# POWER.net
KiCad netlist of a schematic drawn in Altium Designer
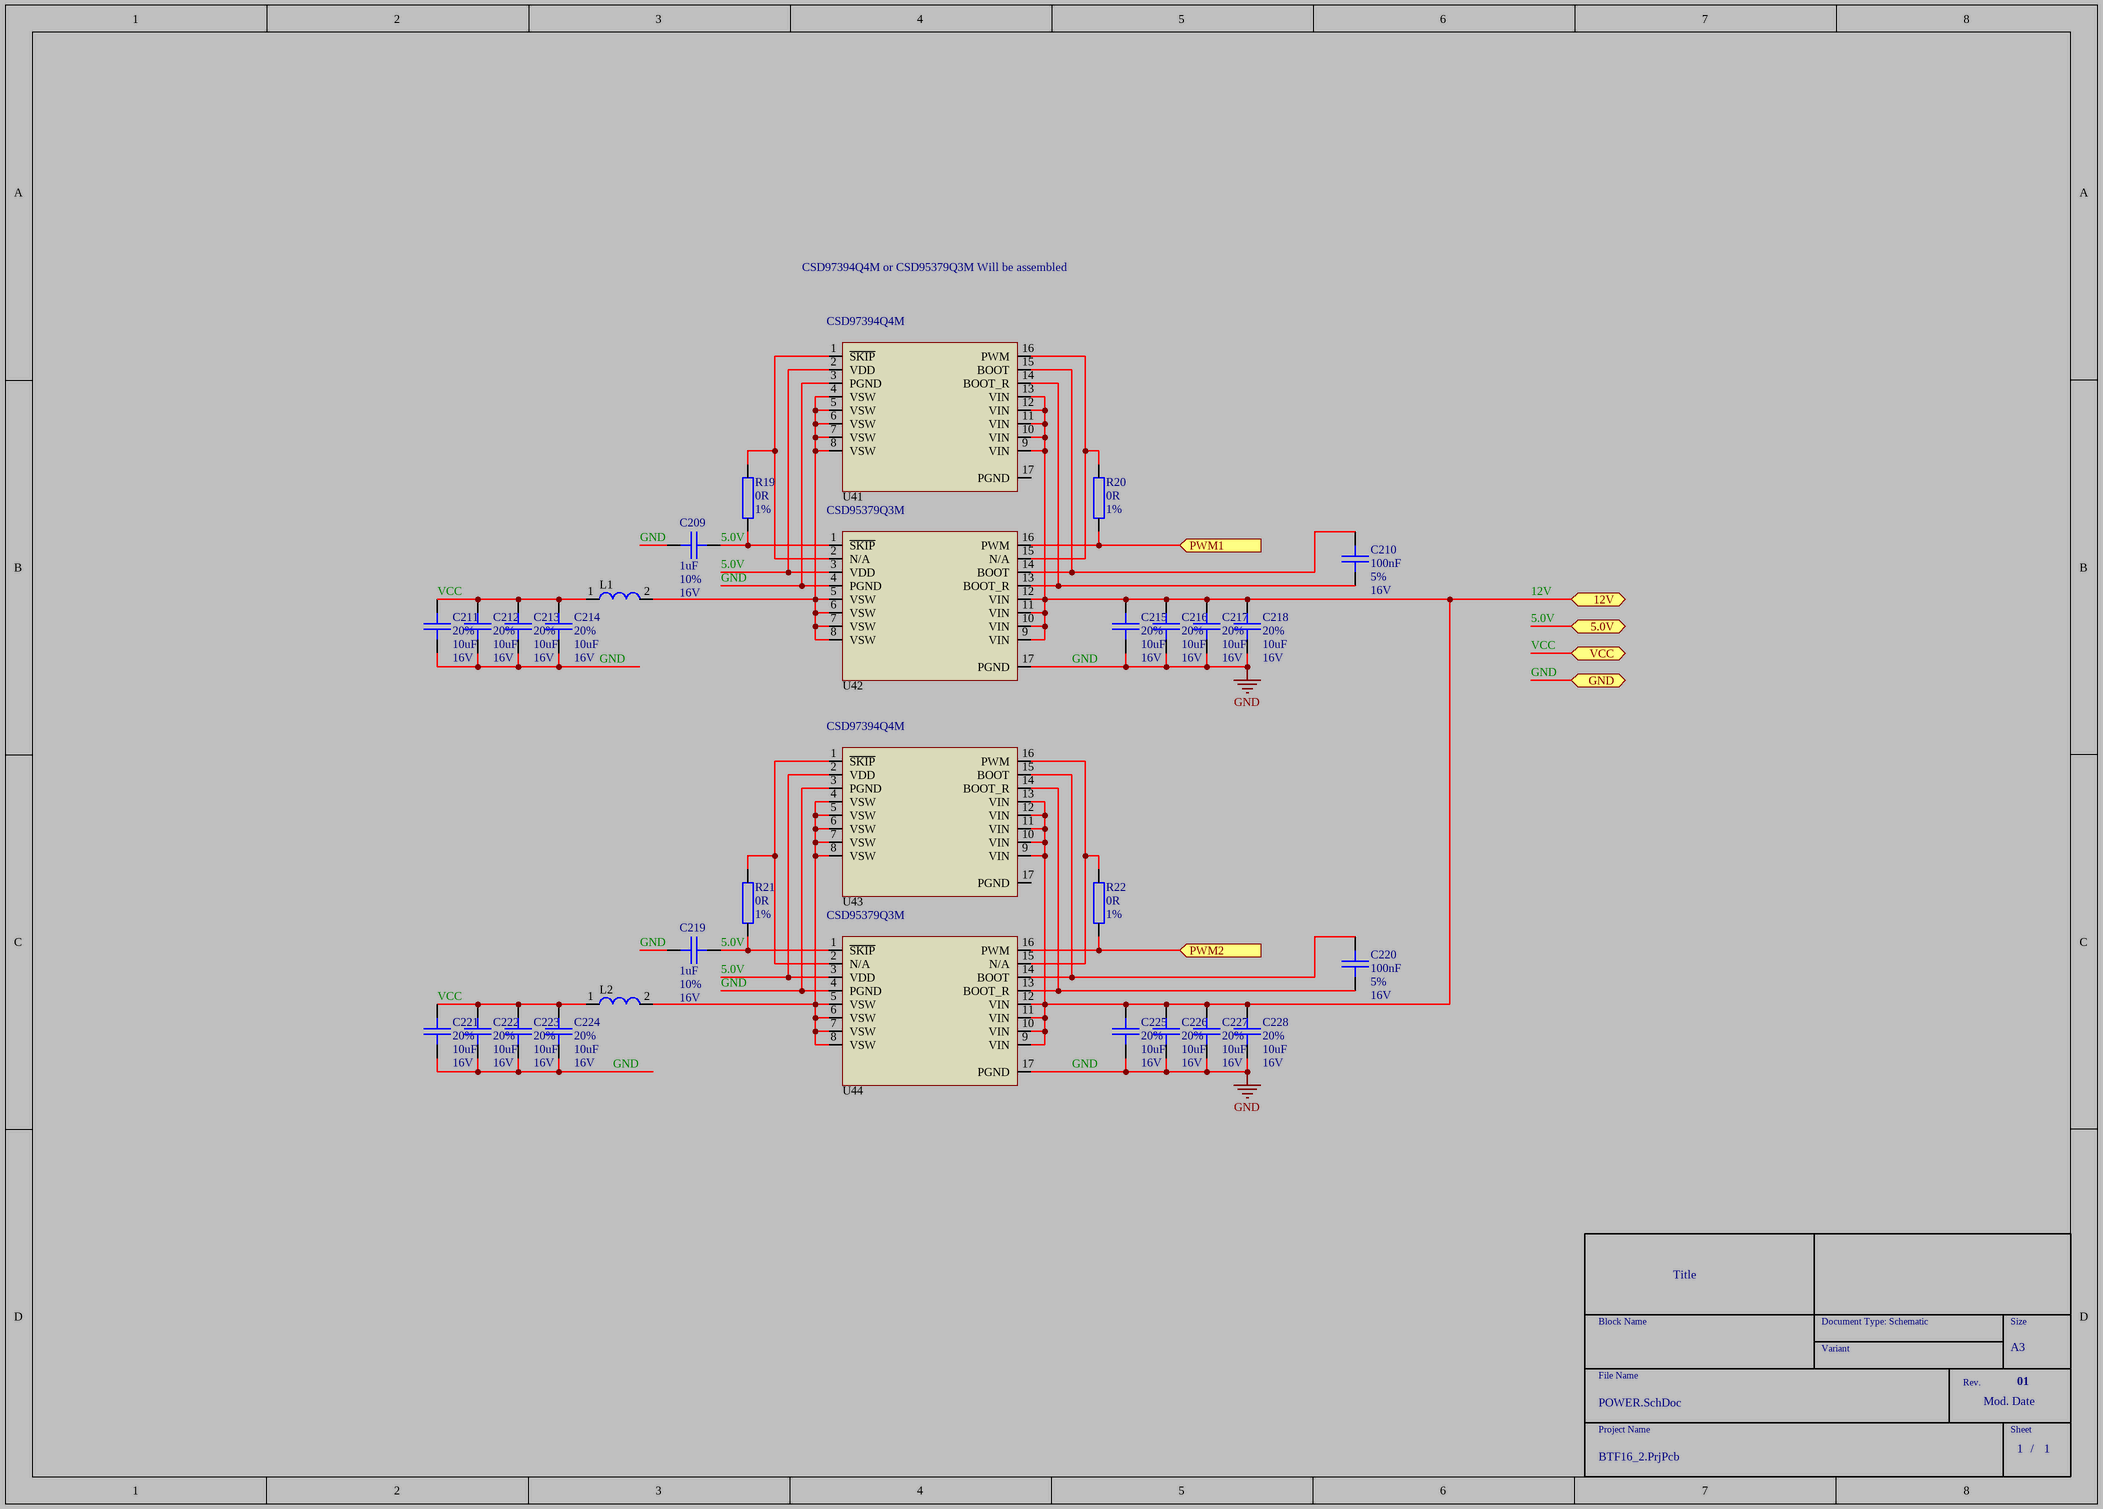
[diagram p0: POWER.SchDoc]

(export (version "E")
  (design (tool "Eeschema 10.0.6"))
  (components
    (comp (ref "C209")
      (value "C")
      (footprint "SMD_0603_CAPC1608X95N")
      (fields
        (field (name "DB_PART_NUMBER") "CAP000023307")
        (field (name "DB_VALUE") "1uF")
        (field (name "DB_TOLERANCE") "10%")
        (field (name "DB_VOLTAGE") "16V")
        (field (name "DB_MANUFACTURER_PART") "KEMET    C0603F105K4RAC")
      )
      (libsource (lib "Database_Libs1") (part "C"))
    )
    (comp (ref "C210")
      (value "C")
      (footprint "SMD_0603_CAPC1608X95N")
      (fields
        (field (name "DB_PART_NUMBER") "CAP000027134")
        (field (name "DB_VALUE") "100nF")
        (field (name "DB_TOLERANCE") "5%")
        (field (name "DB_VOLTAGE") "16V")
        (field (name "DB_MANUFACTURER_PART") "KEMET    C0603C104J4RAC")
      )
      (libsource (lib "Database_Libs1") (part "C"))
    )
    (comp (ref "C211")
      (value "C")
      (footprint "SMD_0805_CAPC2012X145N")
      (fields
        (field (name "DB_MANUFACTURER_PART") "KEMET    C0805C106M4PAC")
        (field (name "DB_PART_NUMBER") "CAP000043650")
        (field (name "DB_TOLERANCE") "20%")
        (field (name "DB_VALUE") "10uF")
        (field (name "DB_VOLTAGE") "16V")
      )
      (libsource (lib "Database_Libs1") (part "C"))
    )
    (comp (ref "C212")
      (value "C")
      (footprint "SMD_0805_CAPC2012X145N")
      (fields
        (field (name "DB_MANUFACTURER_PART") "KEMET    C0805C106M4PAC")
        (field (name "DB_PART_NUMBER") "CAP000043650")
        (field (name "DB_TOLERANCE") "20%")
        (field (name "DB_VALUE") "10uF")
        (field (name "DB_VOLTAGE") "16V")
      )
      (libsource (lib "Database_Libs1") (part "C"))
    )
    (comp (ref "C213")
      (value "C")
      (footprint "SMD_0805_CAPC2012X145N")
      (fields
        (field (name "DB_MANUFACTURER_PART") "KEMET    C0805C106M4PAC")
        (field (name "DB_PART_NUMBER") "CAP000043650")
        (field (name "DB_TOLERANCE") "20%")
        (field (name "DB_VALUE") "10uF")
        (field (name "DB_VOLTAGE") "16V")
      )
      (libsource (lib "Database_Libs1") (part "C"))
    )
    (comp (ref "C214")
      (value "C")
      (footprint "SMD_0805_CAPC2012X145N")
      (fields
        (field (name "DB_MANUFACTURER_PART") "KEMET    C0805C106M4PAC")
        (field (name "DB_PART_NUMBER") "CAP000043650")
        (field (name "DB_TOLERANCE") "20%")
        (field (name "DB_VALUE") "10uF")
        (field (name "DB_VOLTAGE") "16V")
      )
      (libsource (lib "Database_Libs1") (part "C"))
    )
    (comp (ref "C215")
      (value "C")
      (footprint "SMD_0805_CAPC2012X145N")
      (fields
        (field (name "DB_MANUFACTURER_PART") "KEMET    C0805C106M4PAC")
        (field (name "DB_PART_NUMBER") "CAP000043650")
        (field (name "DB_TOLERANCE") "20%")
        (field (name "DB_VALUE") "10uF")
        (field (name "DB_VOLTAGE") "16V")
      )
      (libsource (lib "Database_Libs1") (part "C"))
    )
    (comp (ref "C216")
      (value "C")
      (footprint "SMD_0805_CAPC2012X145N")
      (fields
        (field (name "DB_MANUFACTURER_PART") "KEMET    C0805C106M4PAC")
        (field (name "DB_PART_NUMBER") "CAP000043650")
        (field (name "DB_TOLERANCE") "20%")
        (field (name "DB_VALUE") "10uF")
        (field (name "DB_VOLTAGE") "16V")
      )
      (libsource (lib "Database_Libs1") (part "C"))
    )
    (comp (ref "C217")
      (value "C")
      (footprint "SMD_0805_CAPC2012X145N")
      (fields
        (field (name "DB_MANUFACTURER_PART") "KEMET    C0805C106M4PAC")
        (field (name "DB_PART_NUMBER") "CAP000043650")
        (field (name "DB_TOLERANCE") "20%")
        (field (name "DB_VALUE") "10uF")
        (field (name "DB_VOLTAGE") "16V")
      )
      (libsource (lib "Database_Libs1") (part "C"))
    )
    (comp (ref "C218")
      (value "C")
      (footprint "SMD_0805_CAPC2012X145N")
      (fields
        (field (name "DB_MANUFACTURER_PART") "KEMET    C0805C106M4PAC")
        (field (name "DB_PART_NUMBER") "CAP000043650")
        (field (name "DB_TOLERANCE") "20%")
        (field (name "DB_VALUE") "10uF")
        (field (name "DB_VOLTAGE") "16V")
      )
      (libsource (lib "Database_Libs1") (part "C"))
    )
    (comp (ref "C219")
      (value "C")
      (footprint "SMD_0603_CAPC1608X95N")
      (fields
        (field (name "DB_PART_NUMBER") "CAP000023307")
        (field (name "DB_VALUE") "1uF")
        (field (name "DB_TOLERANCE") "10%")
        (field (name "DB_VOLTAGE") "16V")
        (field (name "DB_MANUFACTURER_PART") "KEMET    C0603F105K4RAC")
      )
      (libsource (lib "Database_Libs1") (part "C"))
    )
    (comp (ref "C220")
      (value "C")
      (footprint "SMD_0603_CAPC1608X95N")
      (fields
        (field (name "DB_PART_NUMBER") "CAP000027134")
        (field (name "DB_VALUE") "100nF")
        (field (name "DB_TOLERANCE") "5%")
        (field (name "DB_VOLTAGE") "16V")
        (field (name "DB_MANUFACTURER_PART") "KEMET    C0603C104J4RAC")
      )
      (libsource (lib "Database_Libs1") (part "C"))
    )
    (comp (ref "C221")
      (value "C")
      (footprint "SMD_0805_CAPC2012X145N")
      (fields
        (field (name "DB_MANUFACTURER_PART") "KEMET    C0805C106M4PAC")
        (field (name "DB_PART_NUMBER") "CAP000043650")
        (field (name "DB_TOLERANCE") "20%")
        (field (name "DB_VALUE") "10uF")
        (field (name "DB_VOLTAGE") "16V")
      )
      (libsource (lib "Database_Libs1") (part "C"))
    )
    (comp (ref "C222")
      (value "C")
      (footprint "SMD_0805_CAPC2012X145N")
      (fields
        (field (name "DB_MANUFACTURER_PART") "KEMET    C0805C106M4PAC")
        (field (name "DB_PART_NUMBER") "CAP000043650")
        (field (name "DB_TOLERANCE") "20%")
        (field (name "DB_VALUE") "10uF")
        (field (name "DB_VOLTAGE") "16V")
      )
      (libsource (lib "Database_Libs1") (part "C"))
    )
    (comp (ref "C223")
      (value "C")
      (footprint "SMD_0805_CAPC2012X145N")
      (fields
        (field (name "DB_MANUFACTURER_PART") "KEMET    C0805C106M4PAC")
        (field (name "DB_PART_NUMBER") "CAP000043650")
        (field (name "DB_TOLERANCE") "20%")
        (field (name "DB_VALUE") "10uF")
        (field (name "DB_VOLTAGE") "16V")
      )
      (libsource (lib "Database_Libs1") (part "C"))
    )
    (comp (ref "C224")
      (value "C")
      (footprint "SMD_0805_CAPC2012X145N")
      (fields
        (field (name "DB_MANUFACTURER_PART") "KEMET    C0805C106M4PAC")
        (field (name "DB_PART_NUMBER") "CAP000043650")
        (field (name "DB_TOLERANCE") "20%")
        (field (name "DB_VALUE") "10uF")
        (field (name "DB_VOLTAGE") "16V")
      )
      (libsource (lib "Database_Libs1") (part "C"))
    )
    (comp (ref "C225")
      (value "C")
      (footprint "SMD_0805_CAPC2012X145N")
      (fields
        (field (name "DB_MANUFACTURER_PART") "KEMET    C0805C106M4PAC")
        (field (name "DB_PART_NUMBER") "CAP000043650")
        (field (name "DB_TOLERANCE") "20%")
        (field (name "DB_VALUE") "10uF")
        (field (name "DB_VOLTAGE") "16V")
      )
      (libsource (lib "Database_Libs1") (part "C"))
    )
    (comp (ref "C226")
      (value "C")
      (footprint "SMD_0805_CAPC2012X145N")
      (fields
        (field (name "DB_MANUFACTURER_PART") "KEMET    C0805C106M4PAC")
        (field (name "DB_PART_NUMBER") "CAP000043650")
        (field (name "DB_TOLERANCE") "20%")
        (field (name "DB_VALUE") "10uF")
        (field (name "DB_VOLTAGE") "16V")
      )
      (libsource (lib "Database_Libs1") (part "C"))
    )
    (comp (ref "C227")
      (value "C")
      (footprint "SMD_0805_CAPC2012X145N")
      (fields
        (field (name "DB_MANUFACTURER_PART") "KEMET    C0805C106M4PAC")
        (field (name "DB_PART_NUMBER") "CAP000043650")
        (field (name "DB_TOLERANCE") "20%")
        (field (name "DB_VALUE") "10uF")
        (field (name "DB_VOLTAGE") "16V")
      )
      (libsource (lib "Database_Libs1") (part "C"))
    )
    (comp (ref "C228")
      (value "C")
      (footprint "SMD_0805_CAPC2012X145N")
      (fields
        (field (name "DB_MANUFACTURER_PART") "KEMET    C0805C106M4PAC")
        (field (name "DB_PART_NUMBER") "CAP000043650")
        (field (name "DB_TOLERANCE") "20%")
        (field (name "DB_VALUE") "10uF")
        (field (name "DB_VOLTAGE") "16V")
      )
      (libsource (lib "Database_Libs1") (part "C"))
    )
    (comp (ref "L1") (value "470nH") (footprint "SMT_INDM135130X800N") (libsource (lib "DLV") (part "L")))
    (comp (ref "L2") (value "470nH") (footprint "SMT_INDM135130X800N") (libsource (lib "DLV") (part "L")))
    (comp (ref "R19")
      (value "R")
      (footprint "SMD_0603_RESC1608X55N")
      (fields
        (field (name "DB_PART_NUMBER") "RES000008926")
        (field (name "DB_VALUE") "0R")
        (field (name "DB_TOLERANCE") "1%")
        (field (name "DB_MANUFACTURER_PART") "YAGEO    AC0603FR-070RL")
        (field (name "DB_APPROVED_BY") "VSN")
      )
      (libsource (lib "Database_Libs1") (part "R"))
    )
    (comp (ref "R20")
      (value "R")
      (footprint "SMD_0603_RESC1608X55N")
      (fields
        (field (name "DB_PART_NUMBER") "RES000008926")
        (field (name "DB_VALUE") "0R")
        (field (name "DB_TOLERANCE") "1%")
        (field (name "DB_MANUFACTURER_PART") "YAGEO    AC0603FR-070RL")
        (field (name "DB_APPROVED_BY") "VSN")
      )
      (libsource (lib "Database_Libs1") (part "R"))
    )
    (comp (ref "R21")
      (value "R")
      (footprint "SMD_0603_RESC1608X55N")
      (fields
        (field (name "DB_PART_NUMBER") "RES000008926")
        (field (name "DB_VALUE") "0R")
        (field (name "DB_TOLERANCE") "1%")
        (field (name "DB_MANUFACTURER_PART") "YAGEO    AC0603FR-070RL")
        (field (name "DB_APPROVED_BY") "VSN")
      )
      (libsource (lib "Database_Libs1") (part "R"))
    )
    (comp (ref "R22")
      (value "R")
      (footprint "SMD_0603_RESC1608X55N")
      (fields
        (field (name "DB_PART_NUMBER") "RES000008926")
        (field (name "DB_VALUE") "0R")
        (field (name "DB_TOLERANCE") "1%")
        (field (name "DB_MANUFACTURER_PART") "YAGEO    AC0603FR-070RL")
        (field (name "DB_APPROVED_BY") "VSN")
      )
      (libsource (lib "Database_Libs1") (part "R"))
    )
    (comp (ref "U41")
      (value "CSD95379Q3M")
      (footprint "SMD_SON40P330X330X100-17N")
      (description "Texas Instrumendts Buck Boost DC-DC")
      (fields
        (field (name "DB_MANUFACTURER_PART") "TEXAS INSTRUMENTS  CSD97394Q4M")
        (field (name "DB_VALUE") "CSD97394Q4M")
      )
      (libsource (lib "BitCoin") (part "IC_CSD97394Q4M"))
    )
    (comp (ref "U42")
      (value "CSD95379Q3M")
      (footprint "SMD_SON40P330X330X100-17N")
      (description "Texas Instrumendts Buck Boost DC-DC")
      (fields
        (field (name "DB_MANUFACTURER_PART") "TEXAS INSTRUMENTS  CSD95379Q3M")
        (field (name "DB_VALUE") "CSD95379Q3M")
      )
      (libsource (lib "BitCoin") (part "IC_CSD95379Q3M"))
    )
    (comp (ref "U43")
      (value "CSD95379Q3M")
      (footprint "SMD_SON40P330X330X100-17N")
      (description "Texas Instrumendts Buck Boost DC-DC")
      (fields
        (field (name "DB_MANUFACTURER_PART") "TEXAS INSTRUMENTS  CSD97394Q4M")
        (field (name "DB_VALUE") "CSD97394Q4M")
      )
      (libsource (lib "BitCoin") (part "IC_CSD97394Q4M"))
    )
    (comp (ref "U44")
      (value "CSD95379Q3M")
      (footprint "SMD_SON40P330X330X100-17N")
      (description "Texas Instrumendts Buck Boost DC-DC")
      (fields
        (field (name "DB_MANUFACTURER_PART") "TEXAS INSTRUMENTS  CSD95379Q3M")
        (field (name "DB_VALUE") "CSD95379Q3M")
      )
      (libsource (lib "BitCoin") (part "IC_CSD95379Q3M"))
    )
  )
  (nets
    (net (code "1") (name "/5.0V") (class "Default")
      (node (ref "C209") (pin "1") (pinfunction "1_1") (pintype "passive"))
      (node (ref "C219") (pin "1") (pinfunction "1_1") (pintype "passive"))
      (node (ref "R19") (pin "1") (pinfunction "1_1") (pintype "passive"))
      (node (ref "R21") (pin "1") (pinfunction "1_1") (pintype "passive"))
      (node (ref "U41") (pin "2") (pinfunction "VDD_2") (pintype "passive"))
      (node (ref "U42") (pin "1") (pinfunction "~{SKIP}_1") (pintype "passive"))
      (node (ref "U42") (pin "3") (pinfunction "VDD_3") (pintype "passive"))
      (node (ref "U43") (pin "2") (pinfunction "VDD_2") (pintype "passive"))
      (node (ref "U44") (pin "1") (pinfunction "~{SKIP}_1") (pintype "passive"))
      (node (ref "U44") (pin "3") (pinfunction "VDD_3") (pintype "passive"))
    )
    (net (code "2") (name "/12V") (class "Default")
      (node (ref "C215") (pin "1") (pinfunction "1_1") (pintype "passive"))
      (node (ref "C216") (pin "1") (pinfunction "1_1") (pintype "passive"))
      (node (ref "C217") (pin "1") (pinfunction "1_1") (pintype "passive"))
      (node (ref "C218") (pin "1") (pinfunction "1_1") (pintype "passive"))
      (node (ref "C225") (pin "1") (pinfunction "1_1") (pintype "passive"))
      (node (ref "C226") (pin "1") (pinfunction "1_1") (pintype "passive"))
      (node (ref "C227") (pin "1") (pinfunction "1_1") (pintype "passive"))
      (node (ref "C228") (pin "1") (pinfunction "1_1") (pintype "passive"))
      (node (ref "U41") (pin "10") (pinfunction "VIN_10") (pintype "passive"))
      (node (ref "U41") (pin "11") (pinfunction "VIN_11") (pintype "passive"))
      (node (ref "U41") (pin "12") (pinfunction "VIN_12") (pintype "passive"))
      (node (ref "U41") (pin "13") (pinfunction "VIN_13") (pintype "passive"))
      (node (ref "U41") (pin "9") (pinfunction "VIN_9") (pintype "passive"))
      (node (ref "U42") (pin "10") (pinfunction "VIN_10") (pintype "passive"))
      (node (ref "U42") (pin "11") (pinfunction "VIN_11") (pintype "passive"))
      (node (ref "U42") (pin "12") (pinfunction "VIN_12") (pintype "passive"))
      (node (ref "U42") (pin "9") (pinfunction "VIN_9") (pintype "passive"))
      (node (ref "U43") (pin "10") (pinfunction "VIN_10") (pintype "passive"))
      (node (ref "U43") (pin "11") (pinfunction "VIN_11") (pintype "passive"))
      (node (ref "U43") (pin "12") (pinfunction "VIN_12") (pintype "passive"))
      (node (ref "U43") (pin "13") (pinfunction "VIN_13") (pintype "passive"))
      (node (ref "U43") (pin "9") (pinfunction "VIN_9") (pintype "passive"))
      (node (ref "U44") (pin "10") (pinfunction "VIN_10") (pintype "passive"))
      (node (ref "U44") (pin "11") (pinfunction "VIN_11") (pintype "passive"))
      (node (ref "U44") (pin "12") (pinfunction "VIN_12") (pintype "passive"))
      (node (ref "U44") (pin "9") (pinfunction "VIN_9") (pintype "passive"))
    )
    (net (code "3") (name "/PWM1") (class "Default")
      (node (ref "R20") (pin "1") (pinfunction "1_1") (pintype "passive"))
      (node (ref "U42") (pin "16") (pinfunction "PWM_16") (pintype "passive"))
    )
    (net (code "4") (name "/PWM2") (class "Default")
      (node (ref "R22") (pin "1") (pinfunction "1_1") (pintype "passive"))
      (node (ref "U44") (pin "16") (pinfunction "PWM_16") (pintype "passive"))
    )
    (net (code "5") (name "/VCC") (class "Default")
      (node (ref "C211") (pin "1") (pinfunction "1_1") (pintype "passive"))
      (node (ref "C212") (pin "1") (pinfunction "1_1") (pintype "passive"))
      (node (ref "C213") (pin "1") (pinfunction "1_1") (pintype "passive"))
      (node (ref "C214") (pin "1") (pinfunction "1_1") (pintype "passive"))
      (node (ref "C221") (pin "1") (pinfunction "1_1") (pintype "passive"))
      (node (ref "C222") (pin "1") (pinfunction "1_1") (pintype "passive"))
      (node (ref "C223") (pin "1") (pinfunction "1_1") (pintype "passive"))
      (node (ref "C224") (pin "1") (pinfunction "1_1") (pintype "passive"))
      (node (ref "L1") (pin "1") (pinfunction "1_1") (pintype "passive"))
      (node (ref "L2") (pin "1") (pinfunction "1_1") (pintype "passive"))
    )
    (net (code "6") (name "GND") (class "Default")
      (node (ref "C209") (pin "2") (pinfunction "2_2") (pintype "passive"))
      (node (ref "C211") (pin "2") (pinfunction "2_2") (pintype "passive"))
      (node (ref "C212") (pin "2") (pinfunction "2_2") (pintype "passive"))
      (node (ref "C213") (pin "2") (pinfunction "2_2") (pintype "passive"))
      (node (ref "C214") (pin "2") (pinfunction "2_2") (pintype "passive"))
      (node (ref "C215") (pin "2") (pinfunction "2_2") (pintype "passive"))
      (node (ref "C216") (pin "2") (pinfunction "2_2") (pintype "passive"))
      (node (ref "C217") (pin "2") (pinfunction "2_2") (pintype "passive"))
      (node (ref "C218") (pin "2") (pinfunction "2_2") (pintype "passive"))
      (node (ref "C219") (pin "2") (pinfunction "2_2") (pintype "passive"))
      (node (ref "C221") (pin "2") (pinfunction "2_2") (pintype "passive"))
      (node (ref "C222") (pin "2") (pinfunction "2_2") (pintype "passive"))
      (node (ref "C223") (pin "2") (pinfunction "2_2") (pintype "passive"))
      (node (ref "C224") (pin "2") (pinfunction "2_2") (pintype "passive"))
      (node (ref "C225") (pin "2") (pinfunction "2_2") (pintype "passive"))
      (node (ref "C226") (pin "2") (pinfunction "2_2") (pintype "passive"))
      (node (ref "C227") (pin "2") (pinfunction "2_2") (pintype "passive"))
      (node (ref "C228") (pin "2") (pinfunction "2_2") (pintype "passive"))
      (node (ref "U41") (pin "3") (pinfunction "PGND_3") (pintype "passive"))
      (node (ref "U42") (pin "17") (pinfunction "PGND_17") (pintype "passive"))
      (node (ref "U42") (pin "4") (pinfunction "PGND_4") (pintype "passive"))
      (node (ref "U43") (pin "3") (pinfunction "PGND_3") (pintype "passive"))
      (node (ref "U44") (pin "17") (pinfunction "PGND_17") (pintype "passive"))
      (node (ref "U44") (pin "4") (pinfunction "PGND_4") (pintype "passive"))
    )
    (net (code "7") (name "Net-(L1-Pad2)") (class "Default")
      (node (ref "L1") (pin "2") (pinfunction "2_2") (pintype "passive"))
      (node (ref "U41") (pin "4") (pinfunction "VSW_4") (pintype "passive"))
      (node (ref "U41") (pin "5") (pinfunction "VSW_5") (pintype "passive"))
      (node (ref "U41") (pin "6") (pinfunction "VSW_6") (pintype "passive"))
      (node (ref "U41") (pin "7") (pinfunction "VSW_7") (pintype "passive"))
      (node (ref "U41") (pin "8") (pinfunction "VSW_8") (pintype "passive"))
      (node (ref "U42") (pin "5") (pinfunction "VSW_5") (pintype "passive"))
      (node (ref "U42") (pin "6") (pinfunction "VSW_6") (pintype "passive"))
      (node (ref "U42") (pin "7") (pinfunction "VSW_7") (pintype "passive"))
      (node (ref "U42") (pin "8") (pinfunction "VSW_8") (pintype "passive"))
    )
    (net (code "8") (name "Net-(L2-Pad2)") (class "Default")
      (node (ref "L2") (pin "2") (pinfunction "2_2") (pintype "passive"))
      (node (ref "U43") (pin "4") (pinfunction "VSW_4") (pintype "passive"))
      (node (ref "U43") (pin "5") (pinfunction "VSW_5") (pintype "passive"))
      (node (ref "U43") (pin "6") (pinfunction "VSW_6") (pintype "passive"))
      (node (ref "U43") (pin "7") (pinfunction "VSW_7") (pintype "passive"))
      (node (ref "U43") (pin "8") (pinfunction "VSW_8") (pintype "passive"))
      (node (ref "U44") (pin "5") (pinfunction "VSW_5") (pintype "passive"))
      (node (ref "U44") (pin "6") (pinfunction "VSW_6") (pintype "passive"))
      (node (ref "U44") (pin "7") (pinfunction "VSW_7") (pintype "passive"))
      (node (ref "U44") (pin "8") (pinfunction "VSW_8") (pintype "passive"))
    )
    (net (code "9") (name "Net-(U41-BOOT)") (class "Default")
      (node (ref "C210") (pin "1") (pinfunction "1_1") (pintype "passive"))
      (node (ref "U41") (pin "15") (pinfunction "BOOT_15") (pintype "passive"))
      (node (ref "U42") (pin "14") (pinfunction "BOOT_14") (pintype "passive"))
    )
    (net (code "10") (name "Net-(U41-BOOT_R)") (class "Default")
      (node (ref "C210") (pin "2") (pinfunction "2_2") (pintype "passive"))
      (node (ref "U41") (pin "14") (pinfunction "BOOT_R_14") (pintype "passive"))
      (node (ref "U42") (pin "13") (pinfunction "BOOT_R_13") (pintype "passive"))
    )
    (net (code "11") (name "Net-(U41-PWM)") (class "Default")
      (node (ref "R20") (pin "2") (pinfunction "2_2") (pintype "passive"))
      (node (ref "U41") (pin "16") (pinfunction "PWM_16") (pintype "passive"))
      (node (ref "U42") (pin "15") (pinfunction "N/A_15") (pintype "passive"))
    )
    (net (code "12") (name "Net-(U41-~{SKIP})") (class "Default")
      (node (ref "R19") (pin "2") (pinfunction "2_2") (pintype "passive"))
      (node (ref "U41") (pin "1") (pinfunction "~{SKIP}_1") (pintype "passive"))
      (node (ref "U42") (pin "2") (pinfunction "N/A_2") (pintype "passive"))
    )
    (net (code "13") (name "Net-(U43-BOOT)") (class "Default")
      (node (ref "C220") (pin "1") (pinfunction "1_1") (pintype "passive"))
      (node (ref "U43") (pin "15") (pinfunction "BOOT_15") (pintype "passive"))
      (node (ref "U44") (pin "14") (pinfunction "BOOT_14") (pintype "passive"))
    )
    (net (code "14") (name "Net-(U43-BOOT_R)") (class "Default")
      (node (ref "C220") (pin "2") (pinfunction "2_2") (pintype "passive"))
      (node (ref "U43") (pin "14") (pinfunction "BOOT_R_14") (pintype "passive"))
      (node (ref "U44") (pin "13") (pinfunction "BOOT_R_13") (pintype "passive"))
    )
    (net (code "15") (name "Net-(U43-PWM)") (class "Default")
      (node (ref "R22") (pin "2") (pinfunction "2_2") (pintype "passive"))
      (node (ref "U43") (pin "16") (pinfunction "PWM_16") (pintype "passive"))
      (node (ref "U44") (pin "15") (pinfunction "N/A_15") (pintype "passive"))
    )
    (net (code "16") (name "Net-(U43-~{SKIP})") (class "Default")
      (node (ref "R21") (pin "2") (pinfunction "2_2") (pintype "passive"))
      (node (ref "U43") (pin "1") (pinfunction "~{SKIP}_1") (pintype "passive"))
      (node (ref "U44") (pin "2") (pinfunction "N/A_2") (pintype "passive"))
    )
    (net (code "17") (name "unconnected-(U41-PGND-Pad17)") (class "Default")
      (node (ref "U41") (pin "17") (pinfunction "PGND_17") (pintype "passive"))
    )
    (net (code "18") (name "unconnected-(U43-PGND-Pad17)") (class "Default")
      (node (ref "U43") (pin "17") (pinfunction "PGND_17") (pintype "passive"))
    )
  )
)
